# STM32F401.net
KiCad netlist of a schematic drawn in Altium Designer
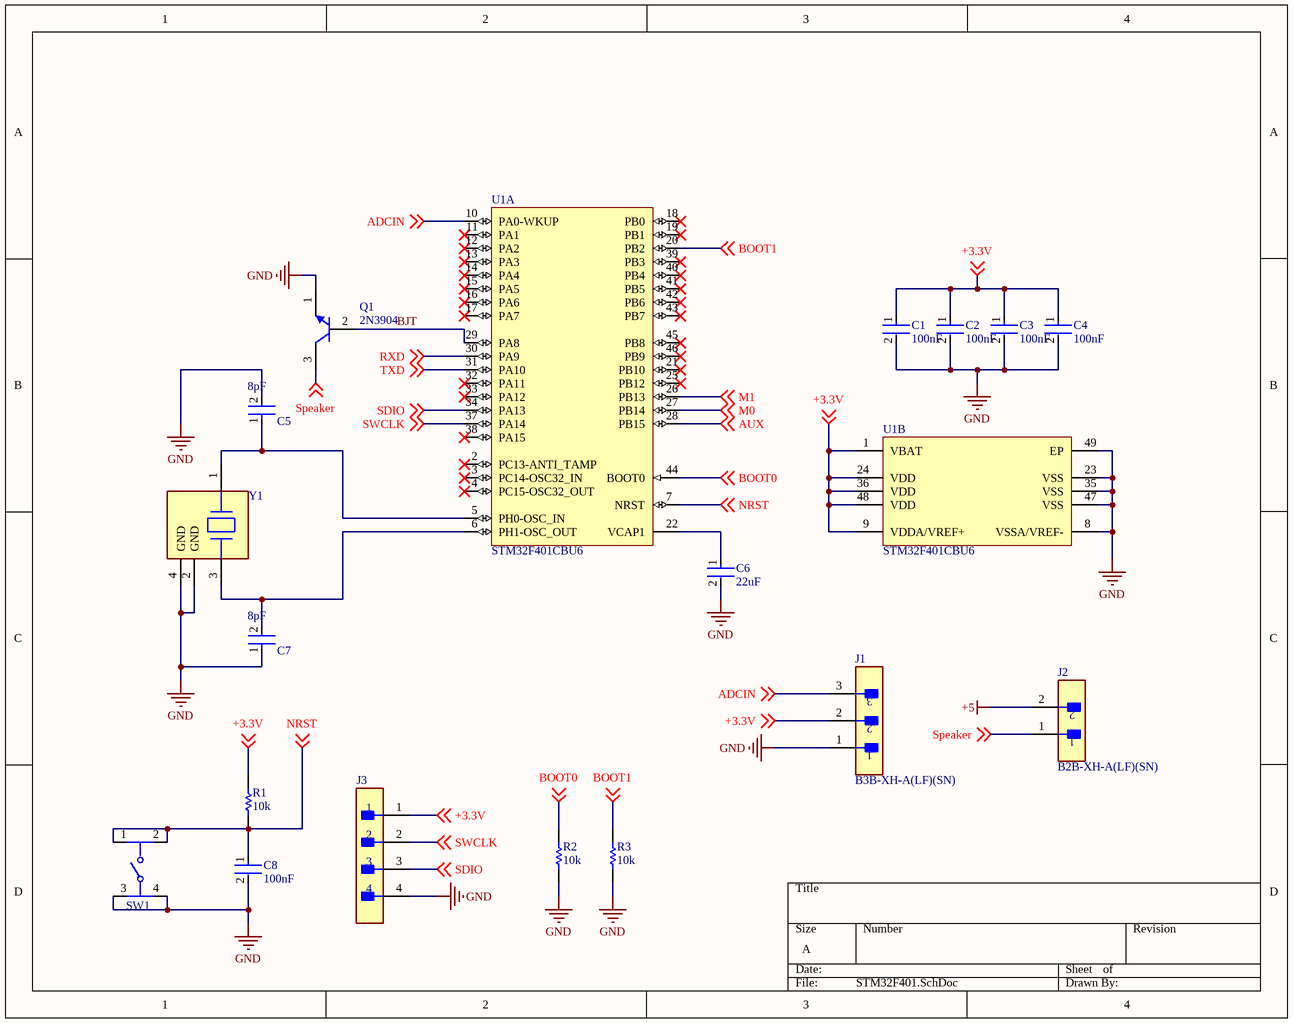
[diagram p0: STM32F401.SchDoc]

(export (version "E")
  (design (tool "Eeschema 10.0.6"))
  (components
    (comp (ref "C1")
      (value "100nF")
      (footprint "FP-CGA3E-0_3-0_1-IPC_A")
      (description "Cap Ceramic 100nF 50V X7R 10% Pad SMD 0603 +125°C Automotive T/R")
      (fields (field (name "TOLERANCE") "10%") (field (name "VOLTAGE") "50V"))
      (libsource (lib "Altium Content Vault") (part "b4654b650e69147ec39a6b967a45e02"))
    )
    (comp (ref "C2")
      (value "100nF")
      (footprint "FP-CGA3E-0_3-0_1-IPC_A")
      (description "Cap Ceramic 100nF 50V X7R 10% Pad SMD 0603 +125°C Automotive T/R")
      (fields (field (name "TOLERANCE") "10%") (field (name "VOLTAGE") "50V"))
      (libsource (lib "Altium Content Vault") (part "b4654b650e69147ec39a6b967a45e02"))
    )
    (comp (ref "C3")
      (value "100nF")
      (footprint "FP-CGA3E-0_3-0_1-IPC_A")
      (description "Cap Ceramic 100nF 50V X7R 10% Pad SMD 0603 +125°C Automotive T/R")
      (fields (field (name "TOLERANCE") "10%") (field (name "VOLTAGE") "50V"))
      (libsource (lib "Altium Content Vault") (part "b4654b650e69147ec39a6b967a45e02"))
    )
    (comp (ref "C4")
      (value "100nF")
      (footprint "FP-CGA3E-0_3-0_1-IPC_A")
      (description "Cap Ceramic 100nF 50V X7R 10% Pad SMD 0603 +125°C Automotive T/R")
      (fields (field (name "TOLERANCE") "10%") (field (name "VOLTAGE") "50V"))
      (libsource (lib "Altium Content Vault") (part "b4654b650e69147ec39a6b967a45e02"))
    )
    (comp (ref "C5")
      (value "8pF")
      (footprint "FP-CGA3E-0_3-0_1-IPC_A")
      (description "Cap Ceramic 8pF 50V C0G 0.5pF Pad SMD 0603 +125°C Automotive T/R")
      (libsource (lib "Altium Content Vault") (part "b4654b650e69147ec39a6b967a45e02"))
    )
    (comp (ref "C6")
      (value "22uF")
      (footprint "FP-GRM188-0_2-MFG")
      (description "Chip Multilayer Ceramic Capacitors for General Purpose, 0603, 22uF, X5R, 15%, 20%, 10V")
      (fields (field (name "TOLERANCE") "20%"))
      (libsource (lib "Altium Content Vault") (part "11868f565c42a9108669ba33697ecf6"))
    )
    (comp (ref "C7")
      (value "8pF")
      (footprint "FP-CGA3E-0_3-0_1-IPC_A")
      (description "Cap Ceramic 8pF 50V C0G 0.5pF Pad SMD 0603 +125°C Automotive T/R")
      (libsource (lib "Altium Content Vault") (part "b4654b650e69147ec39a6b967a45e02"))
    )
    (comp (ref "C8")
      (value "100nF")
      (footprint "FP-CGA3E-0_3-0_1-IPC_A")
      (description "Cap Ceramic 100nF 50V X7R 10% Pad SMD 0603 +125°C Automotive T/R")
      (fields (field (name "TOLERANCE") "10%") (field (name "VOLTAGE") "50V"))
      (libsource (lib "Altium Content Vault") (part "b4654b650e69147ec39a6b967a45e02"))
    )
    (comp (ref "J1")
      (value "B3B-XH-A(LF)(SN)")
      (footprint "FP-B3B-XH-A_LF_SN-MFG")
      (description "CONN HEADER VERT 3POS 2.5MM")
      (libsource (lib "Altium Content Vault") (part "0d3f023dd272f625e17a2be33dea85f"))
    )
    (comp (ref "J2")
      (value "B2B-XH-A(LF)(SN)")
      (footprint "FP-B2B-XH-A_LF_SN-MFG")
      (description "CONN HEADER VERT 2POS 2.5MM")
      (libsource (lib "Altium Content Vault") (part "3bc925449376181038e59eaffc5286c"))
    )
    (comp (ref "J3")
      (value "B04B-XASK-1(LF)(SN)")
      (footprint "FP-B04B-XASK-1_LF_SN-MFG")
      (description "CONN HEADER VERT 4POS 2.5MM")
      (fields
        (field (name "OCTOPART") "https://octopart.com/b04b-xask-1%28lf%29%28sn%29-jst-3990149")
        (field (name "MANUFACTURER") "JST")
      )
      (libsource (lib "Altium Content Vault") (part "299a8cea1bdcbc3624fe62c390fa72c"))
    )
    (comp (ref "Q1")
      (value "2N3904")
      (footprint "ONSC-TO-92-3-29-11")
      (description "General Purpose Transistor, NPN Silicon, 200 mA, 60 V, -55 to 150 degC, 3-Pin TO-92, RoHS, Bulk")
      (fields (field (name "MANUFACTURER") "ONSemiconductor"))
      (libsource (lib "Altium Content Vault") (part "BJT-NPN-EBC-3"))
    )
    (comp (ref "R1")
      (value "10k")
      (footprint "RESC1609X55X30LL15T15")
      (description "Chip Resistor, 10 KOhm, +/- 1%, 0.1 W, -55 to 155 degC, 0603 (1608 Metric), RoHS, Tape and Reel")
      (fields (field (name "TOLERANCE") "1%") (field (name "MANUFACTURER") "Panasonic"))
      (libsource (lib "Altium Content Vault") (part "RES-2"))
    )
    (comp (ref "R2")
      (value "10k")
      (footprint "RESC1609X55X30LL15T15")
      (description "Chip Resistor, 10 KOhm, +/- 1%, 0.1 W, -55 to 155 degC, 0603 (1608 Metric), RoHS, Tape and Reel")
      (fields (field (name "TOLERANCE") "1%") (field (name "MANUFACTURER") "Panasonic"))
      (libsource (lib "Altium Content Vault") (part "RES-2"))
    )
    (comp (ref "R3")
      (value "10k")
      (footprint "RESC1609X55X30LL15T15")
      (description "Chip Resistor, 10 KOhm, +/- 1%, 0.1 W, -55 to 155 degC, 0603 (1608 Metric), RoHS, Tape and Reel")
      (fields (field (name "TOLERANCE") "1%") (field (name "MANUFACTURER") "Panasonic"))
      (libsource (lib "Altium Content Vault") (part "RES-2"))
    )
    (comp (ref "SW1")
      (value "PTS645SH50SMTR92LFS")
      (footprint "FP-PTS645SH50SMTR92LFS-MFG")
      (description "SWITCH TACTILE SPST-NO 0.05A 12V")
      (libsource (lib "Altium Content Vault") (part "1adf0dd01260c80cf25a44bfd6b99ba"))
    )
    (comp (ref "U1")
      (value "STM32F401CBU6")
      (footprint "STM-UFQFPN48_M")
      (fields (field (name "MANUFACTURER") "STMicroelectronics"))
      (libsource (lib "Altium Content Vault") (part "MC-ARM-STM32F401-SQ48"))
    )
    (comp (ref "Y1")
      (value "CX2016DB40000D0FLJCC")
      (footprint "FP-CX2016DB-MFG")
      (description "CRYSTAL 40.0000MHZ 8PF SMD")
      (fields
        (field (name "TOLERANCE") "15ppm")
        (field (name "OCTOPART") "https://octopart.com/cx2016db40000d0fljcc-avx+%2F+kyocera-71139660")
      )
      (libsource (lib "Altium Content Vault") (part "28df8d7a1f20b35eca55ec9e48b468b"))
    )
  )
  (nets
    (net (code "1") (name "+3.3V") (class "Default")
      (node (ref "C1") (pin "1") (pinfunction "1_1") (pintype "passive"))
      (node (ref "C2") (pin "1") (pinfunction "1_1") (pintype "passive"))
      (node (ref "C3") (pin "1") (pinfunction "1_1") (pintype "passive"))
      (node (ref "C4") (pin "1") (pinfunction "1_1") (pintype "passive"))
      (node (ref "J1") (pin "2") (pinfunction "2_2") (pintype "passive"))
      (node (ref "J3") (pin "1") (pinfunction "1_1") (pintype "passive"))
      (node (ref "R1") (pin "2") (pinfunction "2_2") (pintype "passive"))
      (node (ref "U1") (pin "1") (pinfunction "VBAT_1") (pintype "power_in"))
      (node (ref "U1") (pin "24") (pinfunction "VDD_24") (pintype "power_in"))
      (node (ref "U1") (pin "36") (pinfunction "VDD_36") (pintype "power_in"))
      (node (ref "U1") (pin "48") (pinfunction "VDD_48") (pintype "power_in"))
      (node (ref "U1") (pin "9") (pinfunction "VDDA/VREF+_9") (pintype "power_in"))
    )
    (net (code "2") (name "+5") (class "Default")
      (node (ref "J2") (pin "2") (pinfunction "2_2") (pintype "passive"))
    )
    (net (code "3") (name "/BJT") (class "Default")
      (node (ref "Q1") (pin "2") (pinfunction "B_2") (pintype "passive"))
      (node (ref "U1") (pin "29") (pinfunction "PA8_29") (pintype "bidirectional"))
    )
    (net (code "4") (name "ADCIN") (class "Default")
      (node (ref "J1") (pin "3") (pinfunction "3_3") (pintype "passive"))
      (node (ref "U1") (pin "10") (pinfunction "PA0-WKUP_10") (pintype "bidirectional"))
    )
    (net (code "5") (name "AUX") (class "Default")
      (node (ref "U1") (pin "28") (pinfunction "PB15_28") (pintype "bidirectional"))
    )
    (net (code "6") (name "BOOT0") (class "Default")
      (node (ref "R2") (pin "2") (pinfunction "2_2") (pintype "passive"))
      (node (ref "U1") (pin "44") (pinfunction "BOOT0_44") (pintype "input"))
    )
    (net (code "7") (name "BOOT1") (class "Default")
      (node (ref "R3") (pin "2") (pinfunction "2_2") (pintype "passive"))
      (node (ref "U1") (pin "20") (pinfunction "PB2_20") (pintype "bidirectional"))
    )
    (net (code "8") (name "GND") (class "Default")
      (node (ref "C1") (pin "2") (pinfunction "2_2") (pintype "passive"))
      (node (ref "C2") (pin "2") (pinfunction "2_2") (pintype "passive"))
      (node (ref "C3") (pin "2") (pinfunction "2_2") (pintype "passive"))
      (node (ref "C4") (pin "2") (pinfunction "2_2") (pintype "passive"))
      (node (ref "C5") (pin "2") (pinfunction "2_2") (pintype "passive"))
      (node (ref "C6") (pin "2") (pinfunction "2_2") (pintype "passive"))
      (node (ref "C7") (pin "1") (pinfunction "1_1") (pintype "passive"))
      (node (ref "C8") (pin "2") (pinfunction "2_2") (pintype "passive"))
      (node (ref "J1") (pin "1") (pinfunction "1_1") (pintype "passive"))
      (node (ref "J3") (pin "4") (pinfunction "4_4") (pintype "passive"))
      (node (ref "Q1") (pin "1") (pinfunction "E_1") (pintype "passive"))
      (node (ref "R2") (pin "1") (pinfunction "1_1") (pintype "passive"))
      (node (ref "R3") (pin "1") (pinfunction "1_1") (pintype "passive"))
      (node (ref "SW1") (pin "3") (pinfunction "3_3") (pintype "passive"))
      (node (ref "SW1") (pin "4") (pinfunction "4_4") (pintype "passive"))
      (node (ref "U1") (pin "23") (pinfunction "VSS_23") (pintype "power_in"))
      (node (ref "U1") (pin "35") (pinfunction "VSS_35") (pintype "power_in"))
      (node (ref "U1") (pin "47") (pinfunction "VSS_47") (pintype "power_in"))
      (node (ref "U1") (pin "49") (pinfunction "EP_49") (pintype "power_in"))
      (node (ref "U1") (pin "8") (pinfunction "VSSA/VREF-_8") (pintype "power_in"))
      (node (ref "Y1") (pin "2") (pinfunction "GND_2") (pintype "power_in"))
      (node (ref "Y1") (pin "4") (pinfunction "GND_4") (pintype "power_in"))
    )
    (net (code "9") (name "M0") (class "Default")
      (node (ref "U1") (pin "27") (pinfunction "PB14_27") (pintype "bidirectional"))
    )
    (net (code "10") (name "M1") (class "Default")
      (node (ref "U1") (pin "26") (pinfunction "PB13_26") (pintype "bidirectional"))
    )
    (net (code "11") (name "NRST") (class "Default")
      (node (ref "C8") (pin "1") (pinfunction "1_1") (pintype "passive"))
      (node (ref "R1") (pin "1") (pinfunction "1_1") (pintype "passive"))
      (node (ref "SW1") (pin "1") (pinfunction "1_1") (pintype "passive"))
      (node (ref "SW1") (pin "2") (pinfunction "2_2") (pintype "passive"))
      (node (ref "U1") (pin "7") (pinfunction "NRST_7") (pintype "bidirectional"))
    )
    (net (code "12") (name "Net-(U1A-PH0-OSC_IN)") (class "Default")
      (node (ref "C5") (pin "1") (pinfunction "1_1") (pintype "passive"))
      (node (ref "U1") (pin "5") (pinfunction "PH0-OSC_IN_5") (pintype "bidirectional"))
      (node (ref "Y1") (pin "1") (pinfunction "1_1") (pintype "passive"))
    )
    (net (code "13") (name "Net-(U1A-PH1-OSC_OUT)") (class "Default")
      (node (ref "C7") (pin "2") (pinfunction "2_2") (pintype "passive"))
      (node (ref "U1") (pin "6") (pinfunction "PH1-OSC_OUT_6") (pintype "bidirectional"))
      (node (ref "Y1") (pin "3") (pinfunction "3_3") (pintype "passive"))
    )
    (net (code "14") (name "Net-(U1A-VCAP1)") (class "Default")
      (node (ref "C6") (pin "1") (pinfunction "1_1") (pintype "passive"))
      (node (ref "U1") (pin "22") (pinfunction "VCAP1_22") (pintype "power_in"))
    )
    (net (code "15") (name "RXD") (class "Default")
      (node (ref "U1") (pin "30") (pinfunction "PA9_30") (pintype "bidirectional"))
    )
    (net (code "16") (name "SDIO") (class "Default")
      (node (ref "J3") (pin "3") (pinfunction "3_3") (pintype "passive"))
      (node (ref "U1") (pin "34") (pinfunction "PA13_34") (pintype "bidirectional"))
    )
    (net (code "17") (name "SWCLK") (class "Default")
      (node (ref "J3") (pin "2") (pinfunction "2_2") (pintype "passive"))
      (node (ref "U1") (pin "37") (pinfunction "PA14_37") (pintype "bidirectional"))
    )
    (net (code "18") (name "Speaker") (class "Default")
      (node (ref "J2") (pin "1") (pinfunction "1_1") (pintype "passive"))
      (node (ref "Q1") (pin "3") (pinfunction "C_3") (pintype "passive"))
    )
    (net (code "19") (name "TXD") (class "Default")
      (node (ref "U1") (pin "31") (pinfunction "PA10_31") (pintype "bidirectional"))
    )
    (net (code "20") (name "unconnected-(U1A-PA1-Pad11)") (class "Default")
      (node (ref "U1") (pin "11") (pinfunction "PA1_11") (pintype "bidirectional+no_connect"))
    )
    (net (code "21") (name "unconnected-(U1A-PA2-Pad12)") (class "Default")
      (node (ref "U1") (pin "12") (pinfunction "PA2_12") (pintype "bidirectional+no_connect"))
    )
    (net (code "22") (name "unconnected-(U1A-PA3-Pad13)") (class "Default")
      (node (ref "U1") (pin "13") (pinfunction "PA3_13") (pintype "bidirectional+no_connect"))
    )
    (net (code "23") (name "unconnected-(U1A-PA4-Pad14)") (class "Default")
      (node (ref "U1") (pin "14") (pinfunction "PA4_14") (pintype "bidirectional+no_connect"))
    )
    (net (code "24") (name "unconnected-(U1A-PA5-Pad15)") (class "Default")
      (node (ref "U1") (pin "15") (pinfunction "PA5_15") (pintype "bidirectional+no_connect"))
    )
    (net (code "25") (name "unconnected-(U1A-PA6-Pad16)") (class "Default")
      (node (ref "U1") (pin "16") (pinfunction "PA6_16") (pintype "bidirectional+no_connect"))
    )
    (net (code "26") (name "unconnected-(U1A-PA7-Pad17)") (class "Default")
      (node (ref "U1") (pin "17") (pinfunction "PA7_17") (pintype "bidirectional+no_connect"))
    )
    (net (code "27") (name "unconnected-(U1A-PA11-Pad32)") (class "Default")
      (node (ref "U1") (pin "32") (pinfunction "PA11_32") (pintype "bidirectional+no_connect"))
    )
    (net (code "28") (name "unconnected-(U1A-PA12-Pad33)") (class "Default")
      (node (ref "U1") (pin "33") (pinfunction "PA12_33") (pintype "bidirectional+no_connect"))
    )
    (net (code "29") (name "unconnected-(U1A-PA15-Pad38)") (class "Default")
      (node (ref "U1") (pin "38") (pinfunction "PA15_38") (pintype "bidirectional+no_connect"))
    )
    (net (code "30") (name "unconnected-(U1A-PB0-Pad18)") (class "Default")
      (node (ref "U1") (pin "18") (pinfunction "PB0_18") (pintype "bidirectional+no_connect"))
    )
    (net (code "31") (name "unconnected-(U1A-PB1-Pad19)") (class "Default")
      (node (ref "U1") (pin "19") (pinfunction "PB1_19") (pintype "bidirectional+no_connect"))
    )
    (net (code "32") (name "unconnected-(U1A-PB3-Pad39)") (class "Default")
      (node (ref "U1") (pin "39") (pinfunction "PB3_39") (pintype "bidirectional+no_connect"))
    )
    (net (code "33") (name "unconnected-(U1A-PB4-Pad40)") (class "Default")
      (node (ref "U1") (pin "40") (pinfunction "PB4_40") (pintype "bidirectional+no_connect"))
    )
    (net (code "34") (name "unconnected-(U1A-PB5-Pad41)") (class "Default")
      (node (ref "U1") (pin "41") (pinfunction "PB5_41") (pintype "bidirectional+no_connect"))
    )
    (net (code "35") (name "unconnected-(U1A-PB6-Pad42)") (class "Default")
      (node (ref "U1") (pin "42") (pinfunction "PB6_42") (pintype "bidirectional+no_connect"))
    )
    (net (code "36") (name "unconnected-(U1A-PB7-Pad43)") (class "Default")
      (node (ref "U1") (pin "43") (pinfunction "PB7_43") (pintype "bidirectional+no_connect"))
    )
    (net (code "37") (name "unconnected-(U1A-PB8-Pad45)") (class "Default")
      (node (ref "U1") (pin "45") (pinfunction "PB8_45") (pintype "bidirectional+no_connect"))
    )
    (net (code "38") (name "unconnected-(U1A-PB9-Pad46)") (class "Default")
      (node (ref "U1") (pin "46") (pinfunction "PB9_46") (pintype "bidirectional+no_connect"))
    )
    (net (code "39") (name "unconnected-(U1A-PB10-Pad21)") (class "Default")
      (node (ref "U1") (pin "21") (pinfunction "PB10_21") (pintype "bidirectional+no_connect"))
    )
    (net (code "40") (name "unconnected-(U1A-PB12-Pad25)") (class "Default")
      (node (ref "U1") (pin "25") (pinfunction "PB12_25") (pintype "bidirectional+no_connect"))
    )
    (net (code "41") (name "unconnected-(U1A-PC13-ANTI_TAMP-Pad2)") (class "Default")
      (node (ref "U1") (pin "2") (pinfunction "PC13-ANTI_TAMP_2") (pintype "bidirectional+no_connect"))
    )
    (net (code "42") (name "unconnected-(U1A-PC14-OSC32_IN-Pad3)") (class "Default")
      (node (ref "U1") (pin "3") (pinfunction "PC14-OSC32_IN_3") (pintype "bidirectional+no_connect"))
    )
    (net (code "43") (name "unconnected-(U1A-PC15-OSC32_OUT-Pad4)") (class "Default")
      (node (ref "U1") (pin "4") (pinfunction "PC15-OSC32_OUT_4") (pintype "bidirectional+no_connect"))
    )
  )
)
